# KMD-1.net
KiCad netlist of a schematic drawn in EAGLE
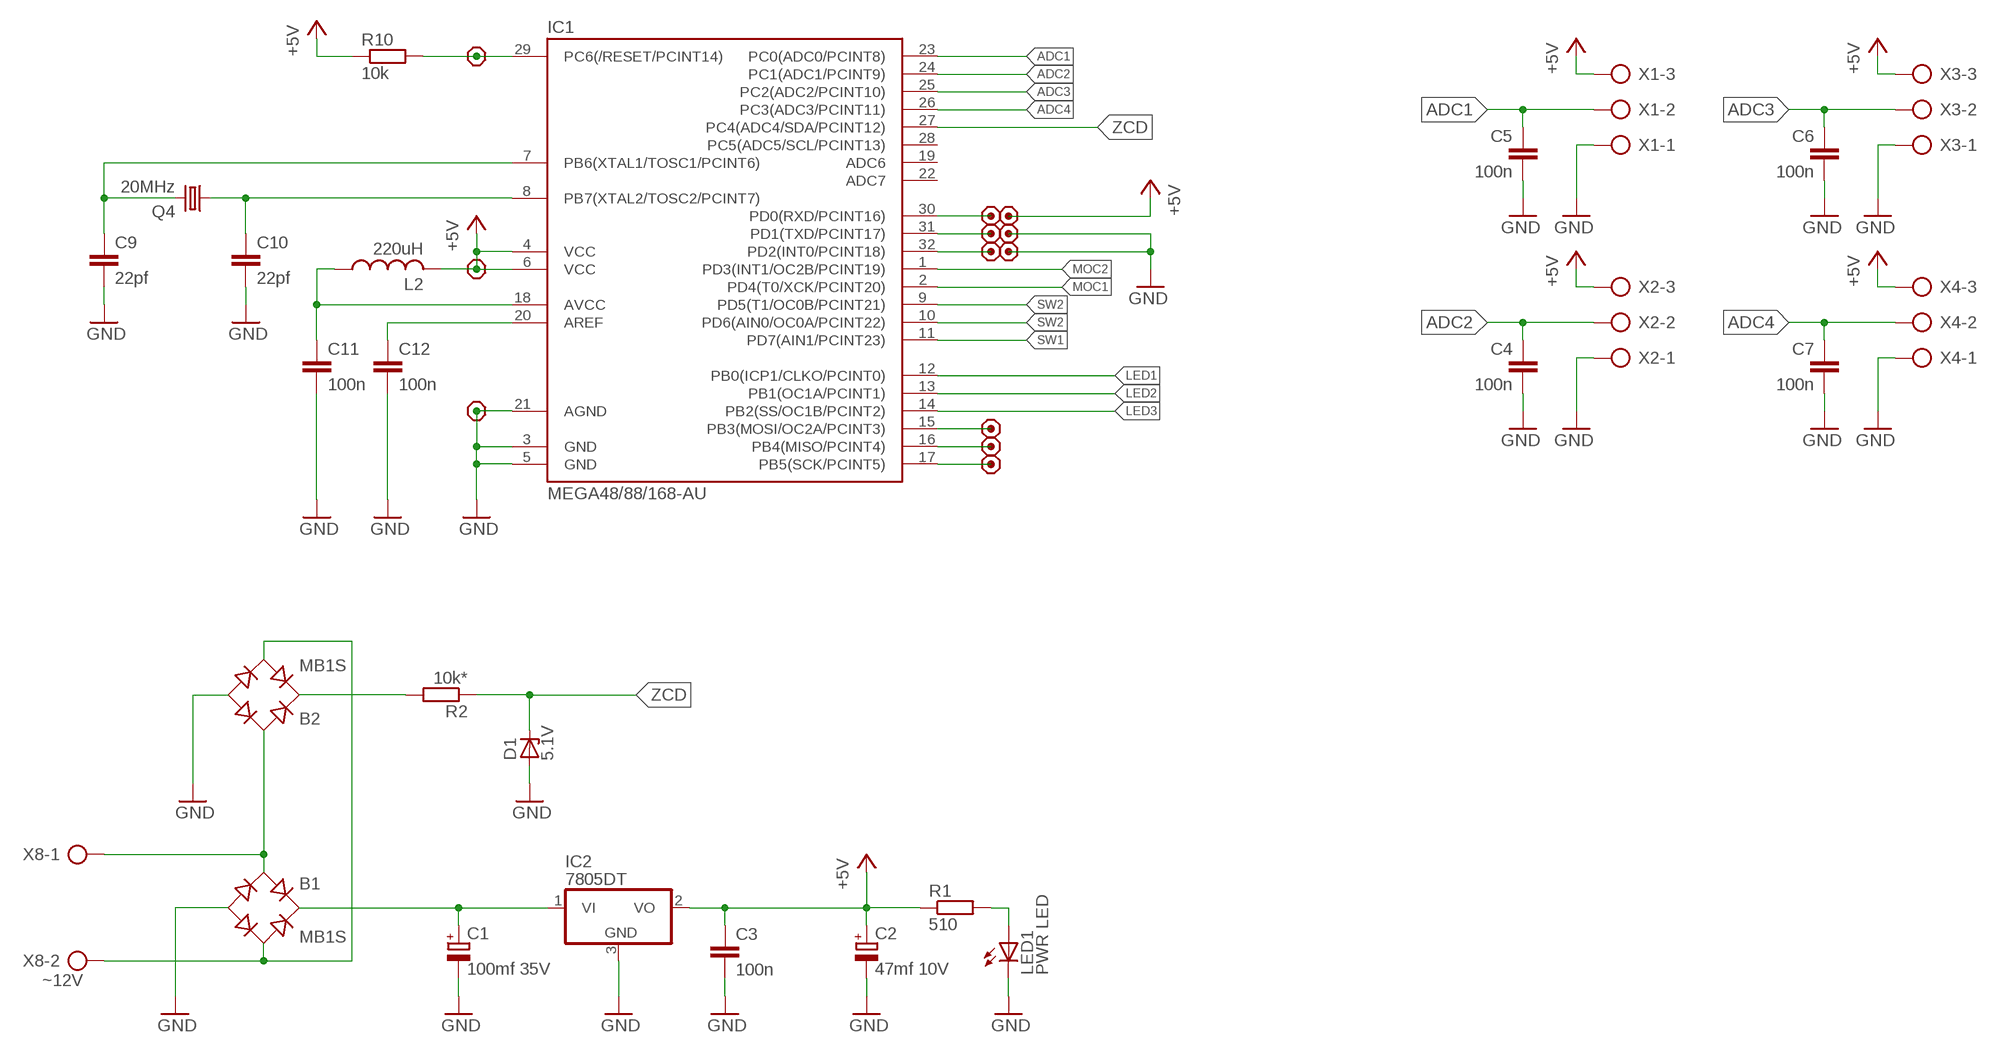
[diagram p0: schematic, sheet 1]

(export (version "E")
  (design (tool "Eeschema 10.0.6"))
  (components
    (comp (ref "B1")
      (value "MB1S")
      (footprint "eagle-import:SOIC-4")
      (libsource (lib "eagle-import") (part "MBS1"))
    )
    (comp (ref "B2")
      (value "MB1S")
      (footprint "eagle-import:SOIC-4")
      (libsource (lib "eagle-import") (part "MBS1"))
    )
    (comp (ref "C1")
      (value "100mf 35V")
      (footprint "eagle-import:E2,5-6")
      (libsource (lib "eagle-import") (part "CPOL-EUE2.5-6"))
    )
    (comp (ref "C2")
      (value "47mf 10V")
      (footprint "eagle-import:E2,5-6")
      (libsource (lib "eagle-import") (part "CPOL-EUE2.5-6"))
    )
    (comp (ref "C3")
      (value "100n")
      (footprint "eagle-import:C0805")
      (libsource (lib "eagle-import") (part "C-EUC0805"))
    )
    (comp (ref "C4")
      (value "100n")
      (footprint "eagle-import:C0805")
      (libsource (lib "eagle-import") (part "C-EUC0805"))
    )
    (comp (ref "C5")
      (value "100n")
      (footprint "eagle-import:C0805")
      (libsource (lib "eagle-import") (part "C-EUC0805"))
    )
    (comp (ref "C6")
      (value "100n")
      (footprint "eagle-import:C0805")
      (libsource (lib "eagle-import") (part "C-EUC0805"))
    )
    (comp (ref "C7")
      (value "100n")
      (footprint "eagle-import:C0805")
      (libsource (lib "eagle-import") (part "C-EUC0805"))
    )
    (comp (ref "C9")
      (value "22pf")
      (footprint "eagle-import:C0805")
      (libsource (lib "eagle-import") (part "C-EUC0805"))
    )
    (comp (ref "C10")
      (value "22pf")
      (footprint "eagle-import:C0805")
      (libsource (lib "eagle-import") (part "C-EUC0805"))
    )
    (comp (ref "C11")
      (value "100n")
      (footprint "eagle-import:C0805")
      (libsource (lib "eagle-import") (part "C-EUC0805"))
    )
    (comp (ref "C12")
      (value "100n")
      (footprint "eagle-import:C0805")
      (libsource (lib "eagle-import") (part "C-EUC0805"))
    )
    (comp (ref "D1")
      (value "5.1V")
      (footprint "eagle-import:DO41Z10")
      (libsource (lib "eagle-import") (part "1N4728"))
    )
    (comp (ref "IC1")
      (value "MEGA48/88/168-AU")
      (footprint "eagle-import:TQFP32-08")
      (libsource (lib "eagle-import") (part "MEGA48/88/168-AU"))
    )
    (comp (ref "IC2")
      (value "7805DT")
      (footprint "eagle-import:TO252")
      (libsource (lib "eagle-import") (part "78DT05"))
    )
    (comp (ref "JP1")
      (value "PIN_1")
      (footprint "eagle-import:1X01")
      (libsource (lib "eagle-import") (part "PIN_1"))
    )
    (comp (ref "JP2")
      (value "PIN_1")
      (footprint "eagle-import:1X01")
      (libsource (lib "eagle-import") (part "PIN_1"))
    )
    (comp (ref "JP3")
      (value "PIN_1")
      (footprint "eagle-import:1X01")
      (libsource (lib "eagle-import") (part "PIN_1"))
    )
    (comp (ref "JP4")
      (value "PIN_1")
      (footprint "eagle-import:1X01")
      (libsource (lib "eagle-import") (part "PIN_1"))
    )
    (comp (ref "JP5")
      (value "PIN_1")
      (footprint "eagle-import:1X01")
      (libsource (lib "eagle-import") (part "PIN_1"))
    )
    (comp (ref "JP6")
      (value "PIN_1")
      (footprint "eagle-import:1X01")
      (libsource (lib "eagle-import") (part "PIN_1"))
    )
    (comp (ref "JP7")
      (value "PIN_1")
      (footprint "eagle-import:1X01")
      (libsource (lib "eagle-import") (part "PIN_1"))
    )
    (comp (ref "JP8")
      (value "PIN_1")
      (footprint "eagle-import:1X01")
      (libsource (lib "eagle-import") (part "PIN_1"))
    )
    (comp (ref "JP9")
      (value "PIN_1")
      (footprint "eagle-import:1X01")
      (libsource (lib "eagle-import") (part "PIN_1"))
    )
    (comp (ref "JP10")
      (value "PIN_1")
      (footprint "eagle-import:1X01")
      (libsource (lib "eagle-import") (part "PIN_1"))
    )
    (comp (ref "JP11")
      (value "PIN_1")
      (footprint "eagle-import:1X01")
      (libsource (lib "eagle-import") (part "PIN_1"))
    )
    (comp (ref "JP12")
      (value "PIN_1")
      (footprint "eagle-import:1X01")
      (libsource (lib "eagle-import") (part "PIN_1"))
    )
    (comp (ref "L2")
      (value "220uH")
      (footprint "eagle-import:0207_5V")
      (libsource (lib "eagle-import") (part "L-US0207/5V"))
    )
    (comp (ref "LED1")
      (value "PWR LED")
      (footprint "eagle-import:LED3MM")
      (libsource (lib "eagle-import") (part "LED3MM"))
    )
    (comp (ref "Q4")
      (value "20MHz")
      (footprint "eagle-import:HC49_S")
      (libsource (lib "eagle-import") (part "CRYSTALHC49S"))
    )
    (comp (ref "R1")
      (value "510")
      (footprint "eagle-import:M0805")
      (libsource (lib "eagle-import") (part "R-EU_M0805"))
    )
    (comp (ref "R2")
      (value "10k*")
      (footprint "eagle-import:M0805")
      (libsource (lib "eagle-import") (part "R-EU_M0805"))
    )
    (comp (ref "R10")
      (value "10k")
      (footprint "eagle-import:M0805")
      (libsource (lib "eagle-import") (part "R-EU_M0805"))
    )
    (comp (ref "X1")
      (value "AK500/3")
      (footprint "eagle-import:AK500_3")
      (libsource (lib "eagle-import") (part "AK500/3"))
    )
    (comp (ref "X2")
      (value "AK500/3")
      (footprint "eagle-import:AK500_3")
      (libsource (lib "eagle-import") (part "AK500/3"))
    )
    (comp (ref "X3")
      (value "AK500/3")
      (footprint "eagle-import:AK500_3")
      (libsource (lib "eagle-import") (part "AK500/3"))
    )
    (comp (ref "X4")
      (value "AK500/3")
      (footprint "eagle-import:AK500_3")
      (libsource (lib "eagle-import") (part "AK500/3"))
    )
    (comp (ref "X8")
      (value "~12V")
      (footprint "eagle-import:AK500_2")
      (fields (field (name "OC_FARNELL") "unknown") (field (name "OC_NEWARK") "unknown"))
      (libsource (lib "eagle-import") (part "AK500/2"))
    )
  )
  (nets
    (net (code "1") (name "+5V") (class "Default")
      (node (ref "C2") (pin "+") (pinfunction "+_+") (pintype "passive"))
      (node (ref "C3") (pin "1") (pinfunction "1_1") (pintype "passive"))
      (node (ref "IC1") (pin "4") (pinfunction "VCC_4") (pintype "power_in"))
      (node (ref "IC1") (pin "6") (pinfunction "VCC_6") (pintype "power_in"))
      (node (ref "IC2") (pin "2") (pinfunction "VO_2") (pintype "passive"))
      (node (ref "JP12") (pin "1") (pinfunction "P$1_1") (pintype "bidirectional"))
      (node (ref "JP8") (pin "1") (pinfunction "P$1_1") (pintype "bidirectional"))
      (node (ref "L2") (pin "2") (pinfunction "2_2") (pintype "passive"))
      (node (ref "R1") (pin "1") (pinfunction "1_1") (pintype "passive"))
      (node (ref "R10") (pin "1") (pinfunction "1_1") (pintype "passive"))
      (node (ref "X1") (pin "3") (pinfunction "KL_3") (pintype "passive"))
      (node (ref "X2") (pin "3") (pinfunction "KL_3") (pintype "passive"))
      (node (ref "X3") (pin "3") (pinfunction "KL_3") (pintype "passive"))
      (node (ref "X4") (pin "3") (pinfunction "KL_3") (pintype "passive"))
    )
    (net (code "2") (name "ADC1") (class "Default")
      (node (ref "C5") (pin "1") (pinfunction "1_1") (pintype "passive"))
      (node (ref "IC1") (pin "23") (pinfunction "PC0(ADC0/PCINT8)_23") (pintype "bidirectional"))
      (node (ref "X1") (pin "2") (pinfunction "KL_2") (pintype "passive"))
    )
    (net (code "3") (name "ADC2") (class "Default")
      (node (ref "C4") (pin "1") (pinfunction "1_1") (pintype "passive"))
      (node (ref "IC1") (pin "24") (pinfunction "PC1(ADC1/PCINT9)_24") (pintype "bidirectional"))
      (node (ref "X2") (pin "2") (pinfunction "KL_2") (pintype "passive"))
    )
    (net (code "4") (name "ADC3") (class "Default")
      (node (ref "C6") (pin "1") (pinfunction "1_1") (pintype "passive"))
      (node (ref "IC1") (pin "25") (pinfunction "PC2(ADC2/PCINT10)_25") (pintype "bidirectional"))
      (node (ref "X3") (pin "2") (pinfunction "KL_2") (pintype "passive"))
    )
    (net (code "5") (name "ADC4") (class "Default")
      (node (ref "C7") (pin "1") (pinfunction "1_1") (pintype "passive"))
      (node (ref "IC1") (pin "26") (pinfunction "PC3(ADC3/PCINT11)_26") (pintype "bidirectional"))
      (node (ref "X4") (pin "2") (pinfunction "KL_2") (pintype "passive"))
    )
    (net (code "6") (name "GND") (class "Default")
      (node (ref "B1") (pin "-") (pinfunction "-_-") (pintype "passive"))
      (node (ref "B2") (pin "-") (pinfunction "-_-") (pintype "passive"))
      (node (ref "C1") (pin "-") (pinfunction "-_-") (pintype "passive"))
      (node (ref "C10") (pin "2") (pinfunction "2_2") (pintype "passive"))
      (node (ref "C11") (pin "2") (pinfunction "2_2") (pintype "passive"))
      (node (ref "C12") (pin "2") (pinfunction "2_2") (pintype "passive"))
      (node (ref "C2") (pin "-") (pinfunction "-_-") (pintype "passive"))
      (node (ref "C3") (pin "2") (pinfunction "2_2") (pintype "passive"))
      (node (ref "C4") (pin "2") (pinfunction "2_2") (pintype "passive"))
      (node (ref "C5") (pin "2") (pinfunction "2_2") (pintype "passive"))
      (node (ref "C6") (pin "2") (pinfunction "2_2") (pintype "passive"))
      (node (ref "C7") (pin "2") (pinfunction "2_2") (pintype "passive"))
      (node (ref "C9") (pin "2") (pinfunction "2_2") (pintype "passive"))
      (node (ref "D1") (pin "A") (pinfunction "A_A") (pintype "passive"))
      (node (ref "IC1") (pin "21") (pinfunction "AGND_21") (pintype "power_in"))
      (node (ref "IC1") (pin "3") (pinfunction "GND_3") (pintype "power_in"))
      (node (ref "IC1") (pin "5") (pinfunction "GND_5") (pintype "power_in"))
      (node (ref "IC2") (pin "3") (pinfunction "GND_3") (pintype "passive"))
      (node (ref "JP10") (pin "1") (pinfunction "P$1_1") (pintype "bidirectional"))
      (node (ref "JP11") (pin "1") (pinfunction "P$1_1") (pintype "bidirectional"))
      (node (ref "JP6") (pin "1") (pinfunction "P$1_1") (pintype "bidirectional"))
      (node (ref "LED1") (pin "K") (pinfunction "C_K") (pintype "passive"))
      (node (ref "X1") (pin "1") (pinfunction "KL_1") (pintype "passive"))
      (node (ref "X2") (pin "1") (pinfunction "KL_1") (pintype "passive"))
      (node (ref "X3") (pin "1") (pinfunction "KL_1") (pintype "passive"))
      (node (ref "X4") (pin "1") (pinfunction "KL_1") (pintype "passive"))
    )
    (net (code "7") (name "LED1") (class "Default")
      (node (ref "IC1") (pin "12") (pinfunction "PB0(ICP1/CLKO/PCINT0)_12") (pintype "bidirectional"))
    )
    (net (code "8") (name "LED2") (class "Default")
      (node (ref "IC1") (pin "13") (pinfunction "PB1(OC1A/PCINT1)_13") (pintype "bidirectional"))
    )
    (net (code "9") (name "LED3") (class "Default")
      (node (ref "IC1") (pin "14") (pinfunction "PB2(SS/OC1B/PCINT2)_14") (pintype "bidirectional"))
    )
    (net (code "10") (name "MOC1") (class "Default")
      (node (ref "IC1") (pin "2") (pinfunction "PD4(T0/XCK/PCINT20)_2") (pintype "bidirectional"))
    )
    (net (code "11") (name "MOC2") (class "Default")
      (node (ref "IC1") (pin "1") (pinfunction "PD3(INT1/OC2B/PCINT19)_1") (pintype "bidirectional"))
    )
    (net (code "12") (name "Net-(B1-AC1)") (class "Default")
      (node (ref "B1") (pin "~1") (pinfunction "AC1_~1") (pintype "passive"))
      (node (ref "B2") (pin "~1") (pinfunction "AC1_~1") (pintype "passive"))
      (node (ref "X8") (pin "1") (pinfunction "KL_1") (pintype "passive"))
    )
    (net (code "13") (name "Net-(B1-AC2)") (class "Default")
      (node (ref "B1") (pin "~2") (pinfunction "AC2_~2") (pintype "passive"))
      (node (ref "B2") (pin "~2") (pinfunction "AC2_~2") (pintype "passive"))
      (node (ref "X8") (pin "2") (pinfunction "KL_2") (pintype "passive"))
    )
    (net (code "14") (name "Net-(B2-Pad+)") (class "Default")
      (node (ref "B2") (pin "+") (pinfunction "+_+") (pintype "passive"))
      (node (ref "R2") (pin "2") (pinfunction "2_2") (pintype "passive"))
    )
    (net (code "15") (name "Net-(IC1-AREF)") (class "Default")
      (node (ref "C12") (pin "1") (pinfunction "1_1") (pintype "passive"))
      (node (ref "IC1") (pin "20") (pinfunction "AREF_20") (pintype "passive"))
    )
    (net (code "16") (name "Net-(IC1-AVCC)") (class "Default")
      (node (ref "C11") (pin "1") (pinfunction "1_1") (pintype "passive"))
      (node (ref "IC1") (pin "18") (pinfunction "AVCC_18") (pintype "passive"))
      (node (ref "L2") (pin "1") (pinfunction "1_1") (pintype "passive"))
    )
    (net (code "17") (name "Net-(IC1-PB3(MOSI{slash}OC2A{slash}PCINT3))") (class "Default")
      (node (ref "IC1") (pin "15") (pinfunction "PB3(MOSI/OC2A/PCINT3)_15") (pintype "bidirectional"))
      (node (ref "JP5") (pin "1") (pinfunction "P$1_1") (pintype "bidirectional"))
    )
    (net (code "18") (name "Net-(IC1-PB4(MISO{slash}PCINT4))") (class "Default")
      (node (ref "IC1") (pin "16") (pinfunction "PB4(MISO/PCINT4)_16") (pintype "bidirectional"))
      (node (ref "JP4") (pin "1") (pinfunction "P$1_1") (pintype "bidirectional"))
    )
    (net (code "19") (name "Net-(IC1-PB5(SCK{slash}PCINT5))") (class "Default")
      (node (ref "IC1") (pin "17") (pinfunction "PB5(SCK/PCINT5)_17") (pintype "bidirectional"))
      (node (ref "JP1") (pin "1") (pinfunction "P$1_1") (pintype "bidirectional"))
    )
    (net (code "20") (name "Net-(IC1-PB6(XTAL1{slash}TOSC1{slash}PCINT6))") (class "Default")
      (node (ref "C9") (pin "1") (pinfunction "1_1") (pintype "passive"))
      (node (ref "IC1") (pin "7") (pinfunction "PB6(XTAL1/TOSC1/PCINT6)_7") (pintype "bidirectional"))
      (node (ref "Q4") (pin "2") (pinfunction "2_2") (pintype "passive"))
    )
    (net (code "21") (name "Net-(IC1-PB7(XTAL2{slash}TOSC2{slash}PCINT7))") (class "Default")
      (node (ref "C10") (pin "1") (pinfunction "1_1") (pintype "passive"))
      (node (ref "IC1") (pin "8") (pinfunction "PB7(XTAL2/TOSC2/PCINT7)_8") (pintype "bidirectional"))
      (node (ref "Q4") (pin "1") (pinfunction "1_1") (pintype "passive"))
    )
    (net (code "22") (name "Net-(IC1-PC6({slash}RESET{slash}PCINT14))") (class "Default")
      (node (ref "IC1") (pin "29") (pinfunction "PC6(/RESET/PCINT14)_29") (pintype "bidirectional"))
      (node (ref "JP9") (pin "1") (pinfunction "P$1_1") (pintype "bidirectional"))
      (node (ref "R10") (pin "2") (pinfunction "2_2") (pintype "passive"))
    )
    (net (code "23") (name "Net-(IC1-PD0(RXD{slash}PCINT16))") (class "Default")
      (node (ref "IC1") (pin "30") (pinfunction "PD0(RXD/PCINT16)_30") (pintype "bidirectional"))
      (node (ref "JP3") (pin "1") (pinfunction "P$1_1") (pintype "bidirectional"))
    )
    (net (code "24") (name "Net-(IC1-PD1(TXD{slash}PCINT17))") (class "Default")
      (node (ref "IC1") (pin "31") (pinfunction "PD1(TXD/PCINT17)_31") (pintype "bidirectional"))
      (node (ref "JP2") (pin "1") (pinfunction "P$1_1") (pintype "bidirectional"))
    )
    (net (code "25") (name "Net-(IC1-PD2(INT0{slash}PCINT18))") (class "Default")
      (node (ref "IC1") (pin "32") (pinfunction "PD2(INT0/PCINT18)_32") (pintype "bidirectional"))
      (node (ref "JP7") (pin "1") (pinfunction "P$1_1") (pintype "bidirectional"))
    )
    (net (code "26") (name "Net-(IC2-VI)") (class "Default")
      (node (ref "B1") (pin "+") (pinfunction "+_+") (pintype "passive"))
      (node (ref "C1") (pin "+") (pinfunction "+_+") (pintype "passive"))
      (node (ref "IC2") (pin "1") (pinfunction "VI_1") (pintype "input"))
    )
    (net (code "27") (name "Net-(LED1-PadA)") (class "Default")
      (node (ref "LED1") (pin "A") (pinfunction "A_A") (pintype "passive"))
      (node (ref "R1") (pin "2") (pinfunction "2_2") (pintype "passive"))
    )
    (net (code "28") (name "SW1") (class "Default")
      (node (ref "IC1") (pin "11") (pinfunction "PD7(AIN1/PCINT23)_11") (pintype "bidirectional"))
    )
    (net (code "29") (name "SW2") (class "Default")
      (node (ref "IC1") (pin "10") (pinfunction "PD6(AIN0/OC0A/PCINT22)_10") (pintype "bidirectional"))
      (node (ref "IC1") (pin "9") (pinfunction "PD5(T1/OC0B/PCINT21)_9") (pintype "bidirectional"))
    )
    (net (code "30") (name "ZCD") (class "Default")
      (node (ref "D1") (pin "C") (pinfunction "C_C") (pintype "passive"))
      (node (ref "IC1") (pin "27") (pinfunction "PC4(ADC4/SDA/PCINT12)_27") (pintype "bidirectional"))
      (node (ref "R2") (pin "1") (pinfunction "1_1") (pintype "passive"))
    )
    (net (code "31") (name "unconnected-(IC1-ADC6-Pad19)") (class "Default")
      (node (ref "IC1") (pin "19") (pinfunction "ADC6_19") (pintype "passive"))
    )
    (net (code "32") (name "unconnected-(IC1-ADC7-Pad22)") (class "Default")
      (node (ref "IC1") (pin "22") (pinfunction "ADC7_22") (pintype "passive"))
    )
    (net (code "33") (name "unconnected-(IC1-PC5(ADC5{slash}SCL{slash}PCINT13)-Pad28)") (class "Default")
      (node (ref "IC1") (pin "28") (pinfunction "PC5(ADC5/SCL/PCINT13)_28") (pintype "bidirectional"))
    )
  )
)
